# S77_Eggbot.net
KiCad netlist of a schematic drawn in EAGLE
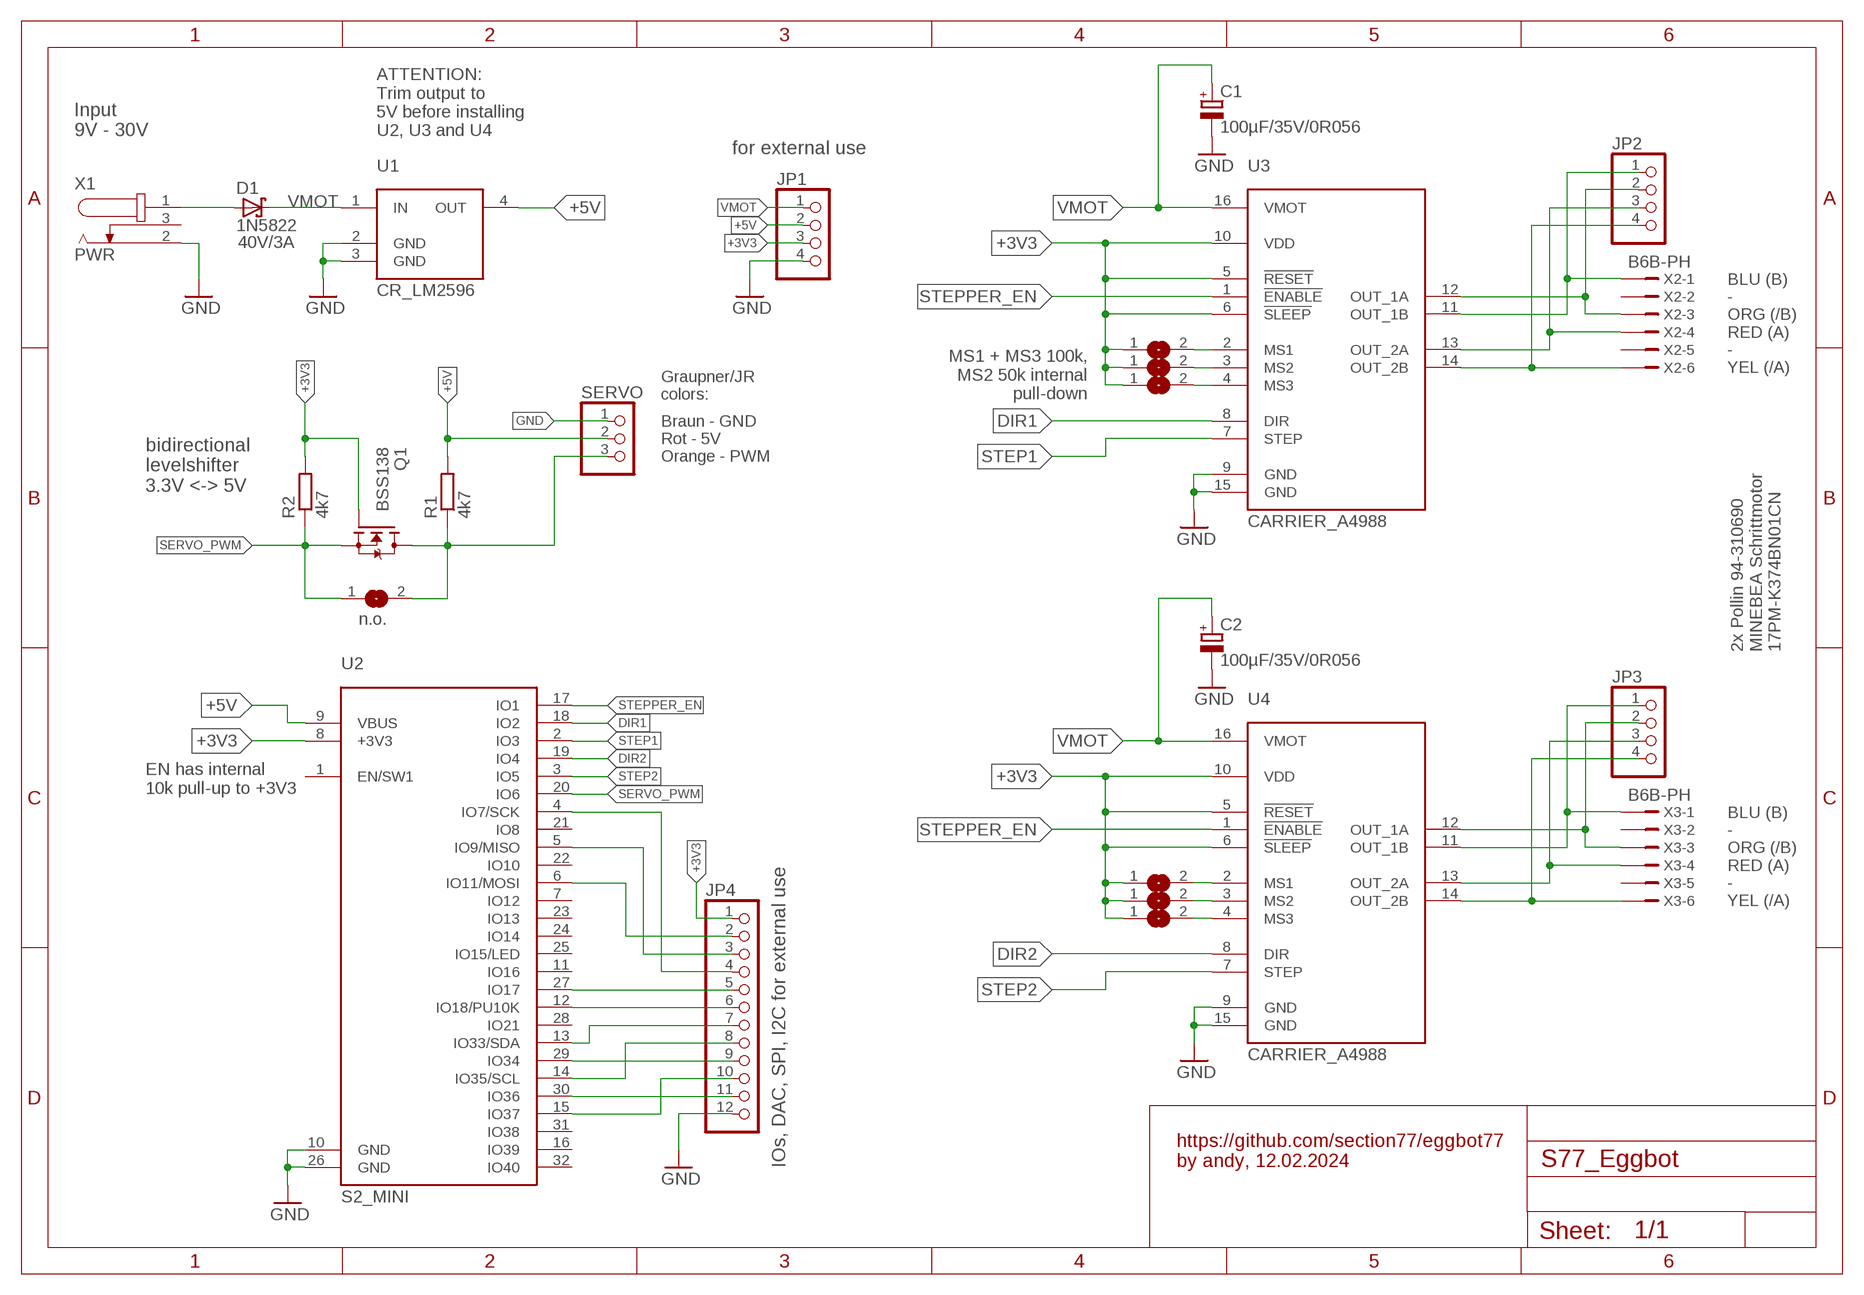
[diagram p0: schematic, sheet 1]

(export (version "E")
  (design (tool "Eeschema 10.0.6"))
  (components
    (comp (ref "C1")
      (value "100µF/35V/0R056")
      (footprint "eagle-import:E3,5-8")
      (fields (field (name "MF") "Panasonic") (field (name "MPN") "EEUFR1V101"))
      (libsource (lib "eagle-import") (part "CPOL-EUE3.5-8"))
    )
    (comp (ref "C2")
      (value "100µF/35V/0R056")
      (footprint "eagle-import:E3,5-8")
      (fields (field (name "MF") "Panasonic") (field (name "MPN") "EEUFR1V101"))
      (libsource (lib "eagle-import") (part "CPOL-EUE3.5-8"))
    )
    (comp (ref "D1")
      (value "1N5822")
      (footprint "eagle-import:DO201T15")
      (libsource (lib "eagle-import") (part "1N5822"))
    )
    (comp (ref "JP1")
      (value "PINHD-1X4")
      (footprint "eagle-import:1X04")
      (libsource (lib "eagle-import") (part "PINHD-1X4"))
    )
    (comp (ref "JP2")
      (value "PINHD-1X4")
      (footprint "eagle-import:1X04")
      (libsource (lib "eagle-import") (part "PINHD-1X4"))
    )
    (comp (ref "JP3")
      (value "PINHD-1X4")
      (footprint "eagle-import:1X04")
      (libsource (lib "eagle-import") (part "PINHD-1X4"))
    )
    (comp (ref "JP4")
      (value "PINHD-1X12")
      (footprint "eagle-import:1X12")
      (libsource (lib "eagle-import") (part "PINHD-1X12"))
    )
    (comp (ref "Q1")
      (value "BSS138")
      (footprint "eagle-import:SOT23")
      (fields (field (name "MF") "Fairchild"))
      (libsource (lib "eagle-import") (part "BSS138"))
    )
    (comp (ref "R1")
      (value "4k7")
      (footprint "eagle-import:R1206")
      (libsource (lib "eagle-import") (part "R-EU_R1206"))
    )
    (comp (ref "R2")
      (value "4k7")
      (footprint "eagle-import:R1206")
      (libsource (lib "eagle-import") (part "R-EU_R1206"))
    )
    (comp (ref "SERVO")
      (value "PINHD-1X3")
      (footprint "eagle-import:1X03")
      (libsource (lib "eagle-import") (part "PINHD-1X3"))
    )
    (comp (ref "SJ1") (value "SJ") (footprint "eagle-import:SJ") (libsource (lib "eagle-import") (part "SJ")))
    (comp (ref "SJ2") (value "SJ") (footprint "eagle-import:SJ") (libsource (lib "eagle-import") (part "SJ")))
    (comp (ref "SJ3") (value "SJ") (footprint "eagle-import:SJ") (libsource (lib "eagle-import") (part "SJ")))
    (comp (ref "SJ4") (value "SJ") (footprint "eagle-import:SJ") (libsource (lib "eagle-import") (part "SJ")))
    (comp (ref "SJ5") (value "SJ") (footprint "eagle-import:SJ") (libsource (lib "eagle-import") (part "SJ")))
    (comp (ref "SJ6") (value "SJ") (footprint "eagle-import:SJ") (libsource (lib "eagle-import") (part "SJ")))
    (comp (ref "SJ7")
      (value "n.o.")
      (footprint "eagle-import:SJ")
      (libsource (lib "eagle-import") (part "SJ"))
    )
    (comp (ref "U1")
      (value "CR_LM2596")
      (footprint "eagle-import:CR_LM2596")
      (libsource (lib "eagle-import") (part "CR_LM2596"))
    )
    (comp (ref "U2")
      (value "S2_MINI")
      (footprint "eagle-import:S2_MINI")
      (libsource (lib "eagle-import") (part "S2_MINI"))
    )
    (comp (ref "U3")
      (value "CARRIER_A4988")
      (footprint "eagle-import:CARRIER_A4988")
      (libsource (lib "eagle-import") (part "CARRIER_A4988"))
    )
    (comp (ref "U4")
      (value "CARRIER_A4988")
      (footprint "eagle-import:CARRIER_A4988")
      (libsource (lib "eagle-import") (part "CARRIER_A4988"))
    )
    (comp (ref "X1")
      (value "PWR")
      (footprint "eagle-import:POLLIN_JACK_A")
      (libsource (lib "eagle-import") (part "POLLIN_JACK_A"))
    )
    (comp (ref "X2")
      (value "B6B-PH")
      (footprint "eagle-import:B6B-PH")
      (libsource (lib "eagle-import") (part "B6B-PH"))
    )
    (comp (ref "X3")
      (value "B6B-PH")
      (footprint "eagle-import:B6B-PH")
      (libsource (lib "eagle-import") (part "B6B-PH"))
    )
  )
  (nets
    (net (code "1") (name "+3V3") (class "Default")
      (node (ref "JP1") (pin "3") (pinfunction "3_3") (pintype "passive"))
      (node (ref "JP4") (pin "1") (pinfunction "1_1") (pintype "passive"))
      (node (ref "Q1") (pin "1") (pinfunction "G_1") (pintype "passive"))
      (node (ref "R2") (pin "2") (pinfunction "2_2") (pintype "passive"))
      (node (ref "SJ1") (pin "1") (pinfunction "1_1") (pintype "passive"))
      (node (ref "SJ2") (pin "1") (pinfunction "1_1") (pintype "passive"))
      (node (ref "SJ3") (pin "1") (pinfunction "1_1") (pintype "passive"))
      (node (ref "SJ4") (pin "1") (pinfunction "1_1") (pintype "passive"))
      (node (ref "SJ5") (pin "1") (pinfunction "1_1") (pintype "passive"))
      (node (ref "SJ6") (pin "1") (pinfunction "1_1") (pintype "passive"))
      (node (ref "U2") (pin "8") (pinfunction "+3V3_8") (pintype "power_in"))
      (node (ref "U3") (pin "10") (pinfunction "VDD_10") (pintype "power_in"))
      (node (ref "U3") (pin "5") (pinfunction "~{RESET}_5") (pintype "input"))
      (node (ref "U3") (pin "6") (pinfunction "~{SLEEP}_6") (pintype "input"))
      (node (ref "U4") (pin "10") (pinfunction "VDD_10") (pintype "power_in"))
      (node (ref "U4") (pin "5") (pinfunction "~{RESET}_5") (pintype "input"))
      (node (ref "U4") (pin "6") (pinfunction "~{SLEEP}_6") (pintype "input"))
    )
    (net (code "2") (name "+5V") (class "Default")
      (node (ref "JP1") (pin "2") (pinfunction "2_2") (pintype "passive"))
      (node (ref "R1") (pin "2") (pinfunction "2_2") (pintype "passive"))
      (node (ref "SERVO") (pin "2") (pinfunction "2_2") (pintype "passive"))
      (node (ref "U1") (pin "4") (pinfunction "OUT_4") (pintype "passive"))
      (node (ref "U2") (pin "9") (pinfunction "VBUS_9") (pintype "power_in"))
    )
    (net (code "3") (name "DIR1") (class "Default")
      (node (ref "U2") (pin "18") (pinfunction "IO2_18") (pintype "bidirectional"))
      (node (ref "U3") (pin "8") (pinfunction "DIR_8") (pintype "input"))
    )
    (net (code "4") (name "DIR2") (class "Default")
      (node (ref "U2") (pin "19") (pinfunction "IO4_19") (pintype "bidirectional"))
      (node (ref "U4") (pin "8") (pinfunction "DIR_8") (pintype "input"))
    )
    (net (code "5") (name "GND") (class "Default")
      (node (ref "C1") (pin "-") (pinfunction "-_-") (pintype "passive"))
      (node (ref "C2") (pin "-") (pinfunction "-_-") (pintype "passive"))
      (node (ref "JP1") (pin "4") (pinfunction "4_4") (pintype "passive"))
      (node (ref "JP4") (pin "12") (pinfunction "12_12") (pintype "passive"))
      (node (ref "SERVO") (pin "1") (pinfunction "1_1") (pintype "passive"))
      (node (ref "U1") (pin "2") (pinfunction "GND_2") (pintype "power_in"))
      (node (ref "U1") (pin "3") (pinfunction "GND_3") (pintype "power_in"))
      (node (ref "U2") (pin "10") (pinfunction "GND_10") (pintype "power_in"))
      (node (ref "U2") (pin "26") (pinfunction "GND_26") (pintype "power_in"))
      (node (ref "U3") (pin "15") (pinfunction "GND_15") (pintype "power_in"))
      (node (ref "U3") (pin "9") (pinfunction "GND_9") (pintype "power_in"))
      (node (ref "U4") (pin "15") (pinfunction "GND_15") (pintype "power_in"))
      (node (ref "U4") (pin "9") (pinfunction "GND_9") (pintype "power_in"))
      (node (ref "X1") (pin "2") (pinfunction "2_2") (pintype "passive"))
    )
    (net (code "6") (name "Net-(D1-PadA)") (class "Default")
      (node (ref "D1") (pin "A") (pinfunction "A_A") (pintype "passive"))
      (node (ref "X1") (pin "1") (pinfunction "1_1") (pintype "passive"))
    )
    (net (code "7") (name "Net-(Q1-D)") (class "Default")
      (node (ref "Q1") (pin "3") (pinfunction "D_3") (pintype "passive"))
      (node (ref "R1") (pin "1") (pinfunction "1_1") (pintype "passive"))
      (node (ref "SERVO") (pin "3") (pinfunction "3_3") (pintype "passive"))
      (node (ref "SJ7") (pin "2") (pinfunction "2_2") (pintype "passive"))
    )
    (net (code "8") (name "Net-(U2-IO7{slash}SCK)") (class "Default")
      (node (ref "JP4") (pin "4") (pinfunction "4_4") (pintype "passive"))
      (node (ref "U2") (pin "4") (pinfunction "IO7/SCK_4") (pintype "bidirectional"))
    )
    (net (code "9") (name "Net-(U2-IO9{slash}MISO)") (class "Default")
      (node (ref "JP4") (pin "3") (pinfunction "3_3") (pintype "passive"))
      (node (ref "U2") (pin "5") (pinfunction "IO9/MISO_5") (pintype "bidirectional"))
    )
    (net (code "10") (name "Net-(U2-IO11{slash}MOSI)") (class "Default")
      (node (ref "JP4") (pin "2") (pinfunction "2_2") (pintype "passive"))
      (node (ref "U2") (pin "6") (pinfunction "IO11/MOSI_6") (pintype "bidirectional"))
    )
    (net (code "11") (name "Net-(U2-IO17)") (class "Default")
      (node (ref "JP4") (pin "5") (pinfunction "5_5") (pintype "passive"))
      (node (ref "U2") (pin "27") (pinfunction "IO17_27") (pintype "bidirectional"))
    )
    (net (code "12") (name "Net-(U2-IO18{slash}PU10K)") (class "Default")
      (node (ref "JP4") (pin "6") (pinfunction "6_6") (pintype "passive"))
      (node (ref "U2") (pin "12") (pinfunction "IO18/PU10K_12") (pintype "bidirectional"))
    )
    (net (code "13") (name "Net-(U2-IO33{slash}SDA)") (class "Default")
      (node (ref "JP4") (pin "7") (pinfunction "7_7") (pintype "passive"))
      (node (ref "U2") (pin "13") (pinfunction "IO33/SDA_13") (pintype "bidirectional"))
    )
    (net (code "14") (name "Net-(U2-IO34)") (class "Default")
      (node (ref "JP4") (pin "9") (pinfunction "9_9") (pintype "passive"))
      (node (ref "U2") (pin "29") (pinfunction "IO34_29") (pintype "bidirectional"))
    )
    (net (code "15") (name "Net-(U2-IO35{slash}SCL)") (class "Default")
      (node (ref "JP4") (pin "8") (pinfunction "8_8") (pintype "passive"))
      (node (ref "U2") (pin "14") (pinfunction "IO35/SCL_14") (pintype "bidirectional"))
    )
    (net (code "16") (name "Net-(U2-IO36)") (class "Default")
      (node (ref "JP4") (pin "11") (pinfunction "11_11") (pintype "passive"))
      (node (ref "U2") (pin "30") (pinfunction "IO36_30") (pintype "bidirectional"))
    )
    (net (code "17") (name "Net-(U2-IO37)") (class "Default")
      (node (ref "JP4") (pin "10") (pinfunction "10_10") (pintype "passive"))
      (node (ref "U2") (pin "15") (pinfunction "IO37_15") (pintype "bidirectional"))
    )
    (net (code "18") (name "Net-(U3-MS1)") (class "Default")
      (node (ref "SJ1") (pin "2") (pinfunction "2_2") (pintype "passive"))
      (node (ref "U3") (pin "2") (pinfunction "MS1_2") (pintype "input"))
    )
    (net (code "19") (name "Net-(U3-MS2)") (class "Default")
      (node (ref "SJ2") (pin "2") (pinfunction "2_2") (pintype "passive"))
      (node (ref "U3") (pin "3") (pinfunction "MS2_3") (pintype "input"))
    )
    (net (code "20") (name "Net-(U3-MS3)") (class "Default")
      (node (ref "SJ3") (pin "2") (pinfunction "2_2") (pintype "passive"))
      (node (ref "U3") (pin "4") (pinfunction "MS3_4") (pintype "input"))
    )
    (net (code "21") (name "Net-(U3-OUT_1A)") (class "Default")
      (node (ref "JP2") (pin "2") (pinfunction "2_2") (pintype "passive"))
      (node (ref "U3") (pin "12") (pinfunction "OUT_1A_12") (pintype "output"))
      (node (ref "X2") (pin "3") (pinfunction "1_3") (pintype "passive"))
    )
    (net (code "22") (name "Net-(U3-OUT_1B)") (class "Default")
      (node (ref "JP2") (pin "1") (pinfunction "1_1") (pintype "passive"))
      (node (ref "U3") (pin "11") (pinfunction "OUT_1B_11") (pintype "output"))
      (node (ref "X2") (pin "1") (pinfunction "1_1") (pintype "passive"))
    )
    (net (code "23") (name "Net-(U3-OUT_2A)") (class "Default")
      (node (ref "JP2") (pin "3") (pinfunction "3_3") (pintype "passive"))
      (node (ref "U3") (pin "13") (pinfunction "OUT_2A_13") (pintype "output"))
      (node (ref "X2") (pin "4") (pinfunction "1_4") (pintype "passive"))
    )
    (net (code "24") (name "Net-(U3-OUT_2B)") (class "Default")
      (node (ref "JP2") (pin "4") (pinfunction "4_4") (pintype "passive"))
      (node (ref "U3") (pin "14") (pinfunction "OUT_2B_14") (pintype "output"))
      (node (ref "X2") (pin "6") (pinfunction "1_6") (pintype "passive"))
    )
    (net (code "25") (name "Net-(U4-MS1)") (class "Default")
      (node (ref "SJ4") (pin "2") (pinfunction "2_2") (pintype "passive"))
      (node (ref "U4") (pin "2") (pinfunction "MS1_2") (pintype "input"))
    )
    (net (code "26") (name "Net-(U4-MS2)") (class "Default")
      (node (ref "SJ5") (pin "2") (pinfunction "2_2") (pintype "passive"))
      (node (ref "U4") (pin "3") (pinfunction "MS2_3") (pintype "input"))
    )
    (net (code "27") (name "Net-(U4-MS3)") (class "Default")
      (node (ref "SJ6") (pin "2") (pinfunction "2_2") (pintype "passive"))
      (node (ref "U4") (pin "4") (pinfunction "MS3_4") (pintype "input"))
    )
    (net (code "28") (name "Net-(U4-OUT_1A)") (class "Default")
      (node (ref "JP3") (pin "2") (pinfunction "2_2") (pintype "passive"))
      (node (ref "U4") (pin "12") (pinfunction "OUT_1A_12") (pintype "output"))
      (node (ref "X3") (pin "3") (pinfunction "1_3") (pintype "passive"))
    )
    (net (code "29") (name "Net-(U4-OUT_1B)") (class "Default")
      (node (ref "JP3") (pin "1") (pinfunction "1_1") (pintype "passive"))
      (node (ref "U4") (pin "11") (pinfunction "OUT_1B_11") (pintype "output"))
      (node (ref "X3") (pin "1") (pinfunction "1_1") (pintype "passive"))
    )
    (net (code "30") (name "Net-(U4-OUT_2A)") (class "Default")
      (node (ref "JP3") (pin "3") (pinfunction "3_3") (pintype "passive"))
      (node (ref "U4") (pin "13") (pinfunction "OUT_2A_13") (pintype "output"))
      (node (ref "X3") (pin "4") (pinfunction "1_4") (pintype "passive"))
    )
    (net (code "31") (name "Net-(U4-OUT_2B)") (class "Default")
      (node (ref "JP3") (pin "4") (pinfunction "4_4") (pintype "passive"))
      (node (ref "U4") (pin "14") (pinfunction "OUT_2B_14") (pintype "output"))
      (node (ref "X3") (pin "6") (pinfunction "1_6") (pintype "passive"))
    )
    (net (code "32") (name "SERVO_PWM") (class "Default")
      (node (ref "Q1") (pin "2") (pinfunction "S_2") (pintype "passive"))
      (node (ref "R2") (pin "1") (pinfunction "1_1") (pintype "passive"))
      (node (ref "SJ7") (pin "1") (pinfunction "1_1") (pintype "passive"))
      (node (ref "U2") (pin "20") (pinfunction "IO6_20") (pintype "bidirectional"))
    )
    (net (code "33") (name "STEP1") (class "Default")
      (node (ref "U2") (pin "2") (pinfunction "IO3_2") (pintype "bidirectional"))
      (node (ref "U3") (pin "7") (pinfunction "STEP_7") (pintype "input"))
    )
    (net (code "34") (name "STEP2") (class "Default")
      (node (ref "U2") (pin "3") (pinfunction "IO5_3") (pintype "bidirectional"))
      (node (ref "U4") (pin "7") (pinfunction "STEP_7") (pintype "input"))
    )
    (net (code "35") (name "STEPPER_EN") (class "Default")
      (node (ref "U2") (pin "17") (pinfunction "IO1_17") (pintype "bidirectional"))
      (node (ref "U3") (pin "1") (pinfunction "~{ENABLE}_1") (pintype "input"))
      (node (ref "U4") (pin "1") (pinfunction "~{ENABLE}_1") (pintype "input"))
    )
    (net (code "36") (name "VMOT") (class "Default")
      (node (ref "C1") (pin "+") (pinfunction "+_+") (pintype "passive"))
      (node (ref "C2") (pin "+") (pinfunction "+_+") (pintype "passive"))
      (node (ref "D1") (pin "C") (pinfunction "C_C") (pintype "passive"))
      (node (ref "JP1") (pin "1") (pinfunction "1_1") (pintype "passive"))
      (node (ref "U1") (pin "1") (pinfunction "IN_1") (pintype "passive"))
      (node (ref "U3") (pin "16") (pinfunction "VMOT_16") (pintype "power_in"))
      (node (ref "U4") (pin "16") (pinfunction "VMOT_16") (pintype "power_in"))
    )
    (net (code "37") (name "unconnected-(U2-EN{slash}SW1-Pad1)") (class "Default")
      (node (ref "U2") (pin "1") (pinfunction "EN/SW1_1") (pintype "bidirectional"))
    )
    (net (code "38") (name "unconnected-(U2-IO8-Pad21)") (class "Default")
      (node (ref "U2") (pin "21") (pinfunction "IO8_21") (pintype "bidirectional"))
    )
    (net (code "39") (name "unconnected-(U2-IO10-Pad22)") (class "Default")
      (node (ref "U2") (pin "22") (pinfunction "IO10_22") (pintype "bidirectional"))
    )
    (net (code "40") (name "unconnected-(U2-IO12-Pad7)") (class "Default")
      (node (ref "U2") (pin "7") (pinfunction "IO12_7") (pintype "bidirectional"))
    )
    (net (code "41") (name "unconnected-(U2-IO13-Pad23)") (class "Default")
      (node (ref "U2") (pin "23") (pinfunction "IO13_23") (pintype "bidirectional"))
    )
    (net (code "42") (name "unconnected-(U2-IO14-Pad24)") (class "Default")
      (node (ref "U2") (pin "24") (pinfunction "IO14_24") (pintype "bidirectional"))
    )
    (net (code "43") (name "unconnected-(U2-IO15{slash}LED-Pad25)") (class "Default")
      (node (ref "U2") (pin "25") (pinfunction "IO15/LED_25") (pintype "bidirectional"))
    )
    (net (code "44") (name "unconnected-(U2-IO16-Pad11)") (class "Default")
      (node (ref "U2") (pin "11") (pinfunction "IO16_11") (pintype "bidirectional"))
    )
    (net (code "45") (name "unconnected-(U2-IO21-Pad28)") (class "Default")
      (node (ref "U2") (pin "28") (pinfunction "IO21_28") (pintype "bidirectional"))
    )
    (net (code "46") (name "unconnected-(U2-IO38-Pad31)") (class "Default")
      (node (ref "U2") (pin "31") (pinfunction "IO38_31") (pintype "bidirectional"))
    )
    (net (code "47") (name "unconnected-(U2-IO39-Pad16)") (class "Default")
      (node (ref "U2") (pin "16") (pinfunction "IO39_16") (pintype "bidirectional"))
    )
    (net (code "48") (name "unconnected-(U2-IO40-Pad32)") (class "Default")
      (node (ref "U2") (pin "32") (pinfunction "IO40_32") (pintype "bidirectional"))
    )
    (net (code "49") (name "unconnected-(X1-Pad3)") (class "Default")
      (node (ref "X1") (pin "3") (pinfunction "3_3") (pintype "passive"))
    )
    (net (code "50") (name "unconnected-(X2B-1-Pad2)") (class "Default")
      (node (ref "X2") (pin "2") (pinfunction "1_2") (pintype "passive"))
    )
    (net (code "51") (name "unconnected-(X2E-1-Pad5)") (class "Default")
      (node (ref "X2") (pin "5") (pinfunction "1_5") (pintype "passive"))
    )
    (net (code "52") (name "unconnected-(X3B-1-Pad2)") (class "Default")
      (node (ref "X3") (pin "2") (pinfunction "1_2") (pintype "passive"))
    )
    (net (code "53") (name "unconnected-(X3E-1-Pad5)") (class "Default")
      (node (ref "X3") (pin "5") (pinfunction "1_5") (pintype "passive"))
    )
  )
)
